# AD9833_Single_Ended.net
KiCad netlist of a schematic drawn in Altium Designer
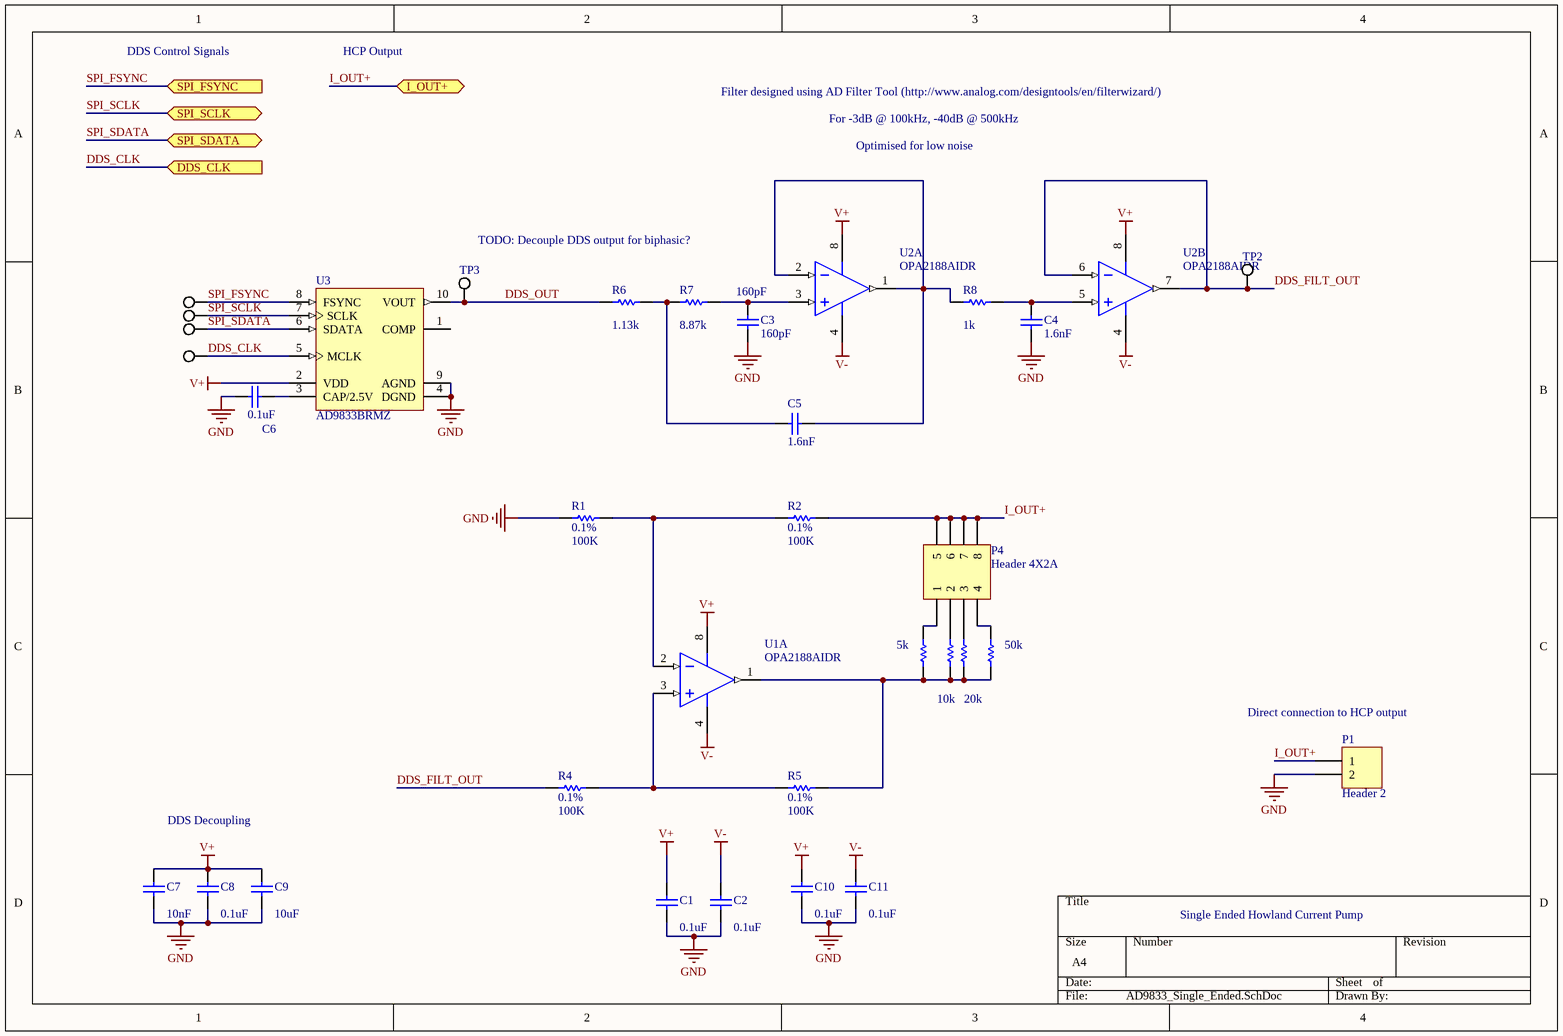
[diagram p0: AD9833_Single_Ended.SchDoc]

(export (version "E")
  (design (tool "Eeschema 10.0.6"))
  (components
    (comp (ref "C1")
      (value "0.1uF")
      (footprint "1608[0603]")
      (description "Capacitor (Semiconductor SIM Model)")
      (fields (field (name "Comment") "Cap Semi") (field (name "PUBLISHER") "Altium Limited"))
      (libsource (lib "Miscellaneous Devices") (part "Cap Semi"))
    )
    (comp (ref "C2")
      (value "0.1uF")
      (footprint "1608[0603]")
      (description "Capacitor (Semiconductor SIM Model)")
      (fields (field (name "Comment") "Cap Semi") (field (name "PUBLISHER") "Altium Limited"))
      (libsource (lib "Miscellaneous Devices") (part "Cap Semi"))
    )
    (comp (ref "C3")
      (value "160pF")
      (footprint "1608[0603]")
      (description "Capacitor (Semiconductor SIM Model)")
      (fields (field (name "ALTIUM_VALUE") "160pF") (field (name "PUBLISHER") "Altium Limited"))
      (libsource (lib "Miscellaneous Devices") (part "Cap Semi"))
    )
    (comp (ref "C4")
      (value "1.6nF")
      (footprint "1608[0603]")
      (description "Capacitor (Semiconductor SIM Model)")
      (fields (field (name "PUBLISHER") "Altium Limited"))
      (libsource (lib "Miscellaneous Devices") (part "Cap Semi"))
    )
    (comp (ref "C5")
      (value "1.6nF")
      (footprint "1608[0603]")
      (description "Capacitor (Semiconductor SIM Model)")
      (fields (field (name "PUBLISHER") "Altium Limited"))
      (libsource (lib "Miscellaneous Devices") (part "Cap Semi"))
    )
    (comp (ref "C6")
      (value "0.1uF")
      (footprint "1608[0603]")
      (description "Capacitor (Semiconductor SIM Model)")
      (fields (field (name "PUBLISHER") "Altium Limited"))
      (libsource (lib "Miscellaneous Devices") (part "Cap Semi"))
    )
    (comp (ref "C7")
      (value "10nF")
      (footprint "1608[0603]")
      (description "Capacitor (Semiconductor SIM Model)")
      (fields (field (name "PUBLISHER") "Altium Limited"))
      (libsource (lib "Miscellaneous Devices") (part "Cap Semi"))
    )
    (comp (ref "C8")
      (value "0.1uF")
      (footprint "1608[0603]")
      (description "Capacitor (Semiconductor SIM Model)")
      (fields (field (name "PUBLISHER") "Altium Limited"))
      (libsource (lib "Miscellaneous Devices") (part "Cap Semi"))
    )
    (comp (ref "C9")
      (value "10uF")
      (footprint "1608[0603]")
      (description "Capacitor (Semiconductor SIM Model)")
      (fields (field (name "PUBLISHER") "Altium Limited"))
      (libsource (lib "Miscellaneous Devices") (part "Cap Semi"))
    )
    (comp (ref "C10")
      (value "0.1uF")
      (footprint "1608[0603]")
      (description "Capacitor (Semiconductor SIM Model)")
      (fields (field (name "PUBLISHER") "Altium Limited"))
      (libsource (lib "Miscellaneous Devices") (part "Cap Semi"))
    )
    (comp (ref "C11")
      (value "0.1uF")
      (footprint "1608[0603]")
      (description "Capacitor (Semiconductor SIM Model)")
      (fields (field (name "PUBLISHER") "Altium Limited"))
      (libsource (lib "Miscellaneous Devices") (part "Cap Semi"))
    )
    (comp (ref "P1")
      (value "Header 2")
      (footprint "HDR1X2")
      (description "Header, 2-Pin")
      (fields (field (name "PUBLISHER") "Altium Limited"))
      (libsource (lib "Miscellaneous Connectors") (part "Header 2"))
    )
    (comp (ref "P4")
      (value "Header 4X2A")
      (footprint "HDR2X4_CEN")
      (description "Header, 4-Pin, Dual row")
      (fields (field (name "PUBLISHER") "Altium Limited"))
      (libsource (lib "Miscellaneous Connectors") (part "Header 4X2A"))
    )
    (comp (ref "R1")
      (value "0.1%")
      (footprint "1608[0603]")
      (description "Resistor")
      (fields (field (name "ALTIUM_VALUE") "100K") (field (name "PUBLISHER") "Altium Limited"))
      (libsource (lib "Miscellaneous Devices") (part "Res1"))
    )
    (comp (ref "R2")
      (value "0.1%")
      (footprint "1608[0603]")
      (description "Resistor")
      (fields (field (name "ALTIUM_VALUE") "100K") (field (name "PUBLISHER") "Altium Limited"))
      (libsource (lib "Miscellaneous Devices") (part "Res1"))
    )
    (comp (ref "R3")
      (value "5k")
      (footprint "1608[0603]")
      (description "Resistor")
      (fields (field (name "PUBLISHER") "Altium Limited"))
      (libsource (lib "Miscellaneous Devices") (part "Res1"))
    )
    (comp (ref "R4")
      (value "0.1%")
      (footprint "1608[0603]")
      (description "Resistor")
      (fields (field (name "ALTIUM_VALUE") "100K") (field (name "PUBLISHER") "Altium Limited"))
      (libsource (lib "Miscellaneous Devices") (part "Res1"))
    )
    (comp (ref "R5")
      (value "0.1%")
      (footprint "1608[0603]")
      (description "Resistor")
      (fields (field (name "ALTIUM_VALUE") "100K") (field (name "PUBLISHER") "Altium Limited"))
      (libsource (lib "Miscellaneous Devices") (part "Res1"))
    )
    (comp (ref "R6")
      (value "1.13k")
      (footprint "1608[0603]")
      (description "Resistor")
      (fields (field (name "PUBLISHER") "Altium Limited"))
      (libsource (lib "Miscellaneous Devices") (part "Res1"))
    )
    (comp (ref "R7")
      (value "8.87k")
      (footprint "1608[0603]")
      (description "Resistor")
      (fields (field (name "PUBLISHER") "Altium Limited"))
      (libsource (lib "Miscellaneous Devices") (part "Res1"))
    )
    (comp (ref "R8")
      (value "1k")
      (footprint "1608[0603]")
      (description "Resistor")
      (fields (field (name "PUBLISHER") "Altium Limited"))
      (libsource (lib "Miscellaneous Devices") (part "Res1"))
    )
    (comp (ref "R10")
      (value "10k")
      (footprint "1608[0603]")
      (description "Resistor")
      (fields (field (name "PUBLISHER") "Altium Limited"))
      (libsource (lib "Miscellaneous Devices") (part "Res1"))
    )
    (comp (ref "R11")
      (value "20k")
      (footprint "1608[0603]")
      (description "Resistor")
      (fields (field (name "PUBLISHER") "Altium Limited"))
      (libsource (lib "Miscellaneous Devices") (part "Res1"))
    )
    (comp (ref "R12")
      (value "50k")
      (footprint "1608[0603]")
      (description "Resistor")
      (fields (field (name "PUBLISHER") "Altium Limited"))
      (libsource (lib "Miscellaneous Devices") (part "Res1"))
    )
    (comp (ref "TP1")
      (value "TESTPOINT_WHITE")
      (footprint "TestPointVia")
      (libsource (lib "altium-import") (part "root_1_TESTPOINT_WHITE_"))
    )
    (comp (ref "TP2")
      (value "TESTPOINT_WHITE")
      (footprint "TestPointVia")
      (libsource (lib "altium-import") (part "root_0_TESTPOINT_WHITE_"))
    )
    (comp (ref "TP3")
      (value "TESTPOINT_WHITE")
      (footprint "TestPointVia")
      (libsource (lib "altium-import") (part "root_0_TESTPOINT_WHITE_"))
    )
    (comp (ref "TP4")
      (value "TESTPOINT_WHITE")
      (footprint "TestPointVia")
      (libsource (lib "altium-import") (part "root_1_TESTPOINT_WHITE_"))
    )
    (comp (ref "TP5")
      (value "TESTPOINT_WHITE")
      (footprint "TestPointVia")
      (libsource (lib "altium-import") (part "root_1_TESTPOINT_WHITE_"))
    )
    (comp (ref "TP6")
      (value "TESTPOINT_WHITE")
      (footprint "TestPointVia")
      (libsource (lib "altium-import") (part "root_1_TESTPOINT_WHITE_"))
    )
    (comp (ref "U1")
      (value "OPA2188AIDR")
      (footprint "D0008A_L")
      (fields (field (name "MANUFACTURER") "Texas Instruments"))
      (libsource (lib "Altium Content Vault") (part "TI-OPA-8_2"))
    )
    (comp (ref "U2")
      (value "OPA2188AIDR")
      (footprint "D0008A_L")
      (fields (field (name "MANUFACTURER") "Texas Instruments"))
      (libsource (lib "Altium Content Vault") (part "TI-OPA-8_2"))
    )
    (comp (ref "U3")
      (value "AD9833BRMZ")
      (footprint "ADI-RM-10_M")
      (libsource (lib "Altium Content Vault") (part "ADI-AD9833-RM-10"))
    )
  )
  (nets
    (net (code "1") (name "/DDS_CLK") (class "Default")
      (node (ref "TP6") (pin "1") (pinfunction "1_1") (pintype "passive"))
      (node (ref "U3") (pin "5") (pinfunction "MCLK_5") (pintype "input"))
    )
    (net (code "2") (name "/DDS_FILT_OUT") (class "Default")
      (node (ref "R4") (pin "1") (pinfunction "1_1") (pintype "passive"))
      (node (ref "TP2") (pin "1") (pinfunction "1_1") (pintype "passive"))
      (node (ref "U2") (pin "6") (pinfunction "IN_B-_6") (pintype "input"))
      (node (ref "U2") (pin "7") (pinfunction "OUT_B_7") (pintype "output"))
    )
    (net (code "3") (name "/DDS_OUT") (class "Default")
      (node (ref "R6") (pin "1") (pinfunction "1_1") (pintype "passive"))
      (node (ref "TP3") (pin "1") (pinfunction "1_1") (pintype "passive"))
      (node (ref "U3") (pin "10") (pinfunction "VOUT_10") (pintype "output"))
    )
    (net (code "4") (name "/I_OUT+") (class "Default")
      (node (ref "P1") (pin "1") (pinfunction "1_1") (pintype "passive"))
      (node (ref "P4") (pin "5") (pinfunction "5_5") (pintype "passive"))
      (node (ref "P4") (pin "6") (pinfunction "6_6") (pintype "passive"))
      (node (ref "P4") (pin "7") (pinfunction "7_7") (pintype "passive"))
      (node (ref "P4") (pin "8") (pinfunction "8_8") (pintype "passive"))
      (node (ref "R2") (pin "2") (pinfunction "2_2") (pintype "passive"))
    )
    (net (code "5") (name "/SPI_FSYNC") (class "Default")
      (node (ref "TP1") (pin "1") (pinfunction "1_1") (pintype "passive"))
      (node (ref "U3") (pin "8") (pinfunction "FSYNC_8") (pintype "input"))
    )
    (net (code "6") (name "/SPI_SCLK") (class "Default")
      (node (ref "TP4") (pin "1") (pinfunction "1_1") (pintype "passive"))
      (node (ref "U3") (pin "7") (pinfunction "SCLK_7") (pintype "input"))
    )
    (net (code "7") (name "/SPI_SDATA") (class "Default")
      (node (ref "TP5") (pin "1") (pinfunction "1_1") (pintype "passive"))
      (node (ref "U3") (pin "6") (pinfunction "SDATA_6") (pintype "input"))
    )
    (net (code "8") (name "GND") (class "Default")
      (node (ref "C1") (pin "1") (pinfunction "1_1") (pintype "passive"))
      (node (ref "C10") (pin "1") (pinfunction "1_1") (pintype "passive"))
      (node (ref "C11") (pin "1") (pinfunction "1_1") (pintype "passive"))
      (node (ref "C2") (pin "1") (pinfunction "1_1") (pintype "passive"))
      (node (ref "C3") (pin "1") (pinfunction "1_1") (pintype "passive"))
      (node (ref "C4") (pin "2") (pinfunction "2_2") (pintype "passive"))
      (node (ref "C6") (pin "1") (pinfunction "1_1") (pintype "passive"))
      (node (ref "C7") (pin "1") (pinfunction "1_1") (pintype "passive"))
      (node (ref "C8") (pin "1") (pinfunction "1_1") (pintype "passive"))
      (node (ref "C9") (pin "1") (pinfunction "1_1") (pintype "passive"))
      (node (ref "P1") (pin "2") (pinfunction "2_2") (pintype "passive"))
      (node (ref "R1") (pin "1") (pinfunction "1_1") (pintype "passive"))
      (node (ref "U3") (pin "4") (pinfunction "DGND_4") (pintype "power_in"))
      (node (ref "U3") (pin "9") (pinfunction "AGND_9") (pintype "power_in"))
    )
    (net (code "9") (name "Net-(C5-Pad2)") (class "Default")
      (node (ref "C5") (pin "2") (pinfunction "2_2") (pintype "passive"))
      (node (ref "R6") (pin "2") (pinfunction "2_2") (pintype "passive"))
      (node (ref "R7") (pin "1") (pinfunction "1_1") (pintype "passive"))
    )
    (net (code "10") (name "Net-(P4-Pad1)") (class "Default")
      (node (ref "P4") (pin "1") (pinfunction "1_1") (pintype "passive"))
      (node (ref "R3") (pin "2") (pinfunction "2_2") (pintype "passive"))
    )
    (net (code "11") (name "Net-(P4-Pad2)") (class "Default")
      (node (ref "P4") (pin "2") (pinfunction "2_2") (pintype "passive"))
      (node (ref "R10") (pin "2") (pinfunction "2_2") (pintype "passive"))
    )
    (net (code "12") (name "Net-(P4-Pad3)") (class "Default")
      (node (ref "P4") (pin "3") (pinfunction "3_3") (pintype "passive"))
      (node (ref "R11") (pin "2") (pinfunction "2_2") (pintype "passive"))
    )
    (net (code "13") (name "Net-(P4-Pad4)") (class "Default")
      (node (ref "P4") (pin "4") (pinfunction "4_4") (pintype "passive"))
      (node (ref "R12") (pin "1") (pinfunction "1_1") (pintype "passive"))
    )
    (net (code "14") (name "Net-(U1A-IN_A+)") (class "Default")
      (node (ref "R4") (pin "2") (pinfunction "2_2") (pintype "passive"))
      (node (ref "R5") (pin "1") (pinfunction "1_1") (pintype "passive"))
      (node (ref "U1") (pin "3") (pinfunction "IN_A+_3") (pintype "input"))
    )
    (net (code "15") (name "Net-(U1A-IN_A-)") (class "Default")
      (node (ref "R1") (pin "2") (pinfunction "2_2") (pintype "passive"))
      (node (ref "R2") (pin "1") (pinfunction "1_1") (pintype "passive"))
      (node (ref "U1") (pin "2") (pinfunction "IN_A-_2") (pintype "input"))
    )
    (net (code "16") (name "Net-(U1A-OUT_A)") (class "Default")
      (node (ref "R10") (pin "1") (pinfunction "1_1") (pintype "passive"))
      (node (ref "R11") (pin "1") (pinfunction "1_1") (pintype "passive"))
      (node (ref "R12") (pin "2") (pinfunction "2_2") (pintype "passive"))
      (node (ref "R3") (pin "1") (pinfunction "1_1") (pintype "passive"))
      (node (ref "R5") (pin "2") (pinfunction "2_2") (pintype "passive"))
      (node (ref "U1") (pin "1") (pinfunction "OUT_A_1") (pintype "output"))
    )
    (net (code "17") (name "Net-(U2A-IN_A+)") (class "Default")
      (node (ref "C3") (pin "2") (pinfunction "2_2") (pintype "passive"))
      (node (ref "R7") (pin "2") (pinfunction "2_2") (pintype "passive"))
      (node (ref "U2") (pin "3") (pinfunction "IN_A+_3") (pintype "input"))
    )
    (net (code "18") (name "Net-(U2A-IN_A-)") (class "Default")
      (node (ref "C5") (pin "1") (pinfunction "1_1") (pintype "passive"))
      (node (ref "R8") (pin "1") (pinfunction "1_1") (pintype "passive"))
      (node (ref "U2") (pin "1") (pinfunction "OUT_A_1") (pintype "output"))
      (node (ref "U2") (pin "2") (pinfunction "IN_A-_2") (pintype "input"))
    )
    (net (code "19") (name "Net-(U2B-IN_B+)") (class "Default")
      (node (ref "C4") (pin "1") (pinfunction "1_1") (pintype "passive"))
      (node (ref "R8") (pin "2") (pinfunction "2_2") (pintype "passive"))
      (node (ref "U2") (pin "5") (pinfunction "IN_B+_5") (pintype "input"))
    )
    (net (code "20") (name "Net-(U3-CAP{slash}2.5V)") (class "Default")
      (node (ref "C6") (pin "2") (pinfunction "2_2") (pintype "passive"))
      (node (ref "U3") (pin "3") (pinfunction "CAP/2.5V_3") (pintype "power_in"))
    )
    (net (code "21") (name "V+") (class "Default")
      (node (ref "C1") (pin "2") (pinfunction "2_2") (pintype "passive"))
      (node (ref "C10") (pin "2") (pinfunction "2_2") (pintype "passive"))
      (node (ref "C7") (pin "2") (pinfunction "2_2") (pintype "passive"))
      (node (ref "C8") (pin "2") (pinfunction "2_2") (pintype "passive"))
      (node (ref "C9") (pin "2") (pinfunction "2_2") (pintype "passive"))
      (node (ref "U1") (pin "8") (pinfunction "V+_8") (pintype "power_in"))
      (node (ref "U2") (pin "8") (pinfunction "V+_8") (pintype "power_in"))
      (node (ref "U3") (pin "2") (pinfunction "VDD_2") (pintype "power_in"))
    )
    (net (code "22") (name "V-") (class "Default")
      (node (ref "C11") (pin "2") (pinfunction "2_2") (pintype "passive"))
      (node (ref "C2") (pin "2") (pinfunction "2_2") (pintype "passive"))
      (node (ref "U1") (pin "4") (pinfunction "V-_4") (pintype "power_in"))
      (node (ref "U2") (pin "4") (pinfunction "V-_4") (pintype "power_in"))
    )
    (net (code "23") (name "unconnected-(U3-COMP-Pad1)") (class "Default")
      (node (ref "U3") (pin "1") (pinfunction "COMP_1") (pintype "passive"))
    )
  )
)
